# Pedal_Display.net
KiCad netlist of a schematic drawn in Altium Designer
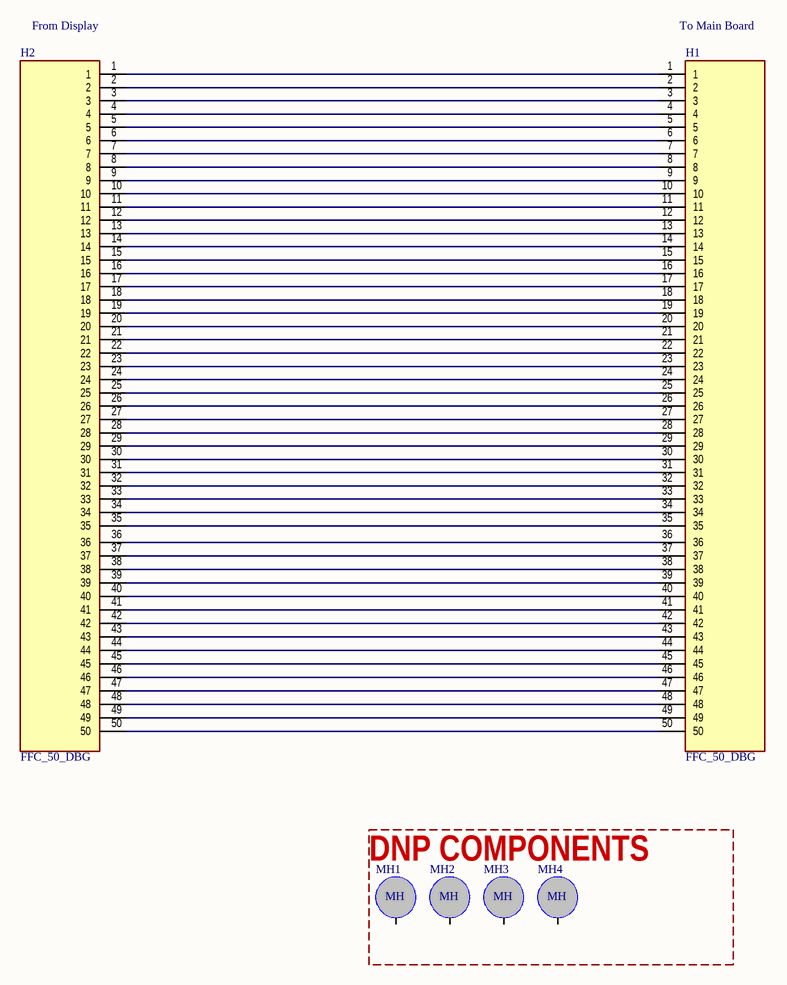
[diagram p0: Pedal_Display.SchDoc]

(export (version "E")
  (design (tool "Eeschema 10.0.6"))
  (components
    (comp (ref "H1")
      (value "FFC_50_DBG")
      (footprint "ProtoStack_H750VBT:FFC_50_DBG")
      (libsource (lib "ProtoStack_H750VBT") (part "FFC_50_DBG"))
    )
    (comp (ref "H2")
      (value "FFC_50_DBG")
      (footprint "ProtoStack_H750VBT:FFC_50_DBG")
      (libsource (lib "") (part "FFC_50_DBG_1"))
    )
    (comp (ref "MH1")
      (value "MountingHole")
      (footprint "ProtoStack_H750VBT:Hole_3mm")
      (libsource (lib "ProtoStack_H750VBT") (part "MountingHole"))
    )
    (comp (ref "MH2")
      (value "MountingHole")
      (footprint "ProtoStack_H750VBT:Hole_3mm")
      (libsource (lib "ProtoStack_H750VBT") (part "MountingHole"))
    )
    (comp (ref "MH3")
      (value "MountingHole")
      (footprint "ProtoStack_H750VBT:Hole_3mm")
      (libsource (lib "ProtoStack_H750VBT") (part "MountingHole"))
    )
    (comp (ref "MH4")
      (value "MountingHole")
      (footprint "ProtoStack_H750VBT:Hole_3mm")
      (libsource (lib "ProtoStack_H750VBT") (part "MountingHole"))
    )
  )
  (nets
    (net (code "1") (name "Net-(H1-Pad1)") (class "Default")
      (node (ref "H1") (pin "1") (pinfunction "1_1") (pintype "passive"))
      (node (ref "H2") (pin "1") (pinfunction "1_1") (pintype "passive"))
    )
    (net (code "2") (name "Net-(H1-Pad2)") (class "Default")
      (node (ref "H1") (pin "2") (pinfunction "2_2") (pintype "passive"))
      (node (ref "H2") (pin "2") (pinfunction "2_2") (pintype "passive"))
    )
    (net (code "3") (name "Net-(H1-Pad3)") (class "Default")
      (node (ref "H1") (pin "3") (pinfunction "3_3") (pintype "passive"))
      (node (ref "H2") (pin "3") (pinfunction "3_3") (pintype "passive"))
    )
    (net (code "4") (name "Net-(H1-Pad4)") (class "Default")
      (node (ref "H1") (pin "4") (pinfunction "4_4") (pintype "passive"))
      (node (ref "H2") (pin "4") (pinfunction "4_4") (pintype "passive"))
    )
    (net (code "5") (name "Net-(H1-Pad5)") (class "Default")
      (node (ref "H1") (pin "5") (pinfunction "5_5") (pintype "passive"))
      (node (ref "H2") (pin "5") (pinfunction "5_5") (pintype "passive"))
    )
    (net (code "6") (name "Net-(H1-Pad6)") (class "Default")
      (node (ref "H1") (pin "6") (pinfunction "6_6") (pintype "passive"))
      (node (ref "H2") (pin "6") (pinfunction "6_6") (pintype "passive"))
    )
    (net (code "7") (name "Net-(H1-Pad7)") (class "Default")
      (node (ref "H1") (pin "7") (pinfunction "7_7") (pintype "passive"))
      (node (ref "H2") (pin "7") (pinfunction "7_7") (pintype "passive"))
    )
    (net (code "8") (name "Net-(H1-Pad8)") (class "Default")
      (node (ref "H1") (pin "8") (pinfunction "8_8") (pintype "passive"))
      (node (ref "H2") (pin "8") (pinfunction "8_8") (pintype "passive"))
    )
    (net (code "9") (name "Net-(H1-Pad9)") (class "Default")
      (node (ref "H1") (pin "9") (pinfunction "9_9") (pintype "passive"))
      (node (ref "H2") (pin "9") (pinfunction "9_9") (pintype "passive"))
    )
    (net (code "10") (name "Net-(H1-Pad10)") (class "Default")
      (node (ref "H1") (pin "10") (pinfunction "10_10") (pintype "passive"))
      (node (ref "H2") (pin "10") (pinfunction "10_10") (pintype "passive"))
    )
    (net (code "11") (name "Net-(H1-Pad11)") (class "Default")
      (node (ref "H1") (pin "11") (pinfunction "11_11") (pintype "passive"))
      (node (ref "H2") (pin "11") (pinfunction "11_11") (pintype "passive"))
    )
    (net (code "12") (name "Net-(H1-Pad12)") (class "Default")
      (node (ref "H1") (pin "12") (pinfunction "12_12") (pintype "passive"))
      (node (ref "H2") (pin "12") (pinfunction "12_12") (pintype "passive"))
    )
    (net (code "13") (name "Net-(H1-Pad13)") (class "Default")
      (node (ref "H1") (pin "13") (pinfunction "13_13") (pintype "passive"))
      (node (ref "H2") (pin "13") (pinfunction "13_13") (pintype "passive"))
    )
    (net (code "14") (name "Net-(H1-Pad14)") (class "Default")
      (node (ref "H1") (pin "14") (pinfunction "14_14") (pintype "passive"))
      (node (ref "H2") (pin "14") (pinfunction "14_14") (pintype "passive"))
    )
    (net (code "15") (name "Net-(H1-Pad15)") (class "Default")
      (node (ref "H1") (pin "15") (pinfunction "15_15") (pintype "passive"))
      (node (ref "H2") (pin "15") (pinfunction "15_15") (pintype "passive"))
    )
    (net (code "16") (name "Net-(H1-Pad16)") (class "Default")
      (node (ref "H1") (pin "16") (pinfunction "16_16") (pintype "passive"))
      (node (ref "H2") (pin "16") (pinfunction "16_16") (pintype "passive"))
    )
    (net (code "17") (name "Net-(H1-Pad17)") (class "Default")
      (node (ref "H1") (pin "17") (pinfunction "17_17") (pintype "passive"))
      (node (ref "H2") (pin "17") (pinfunction "17_17") (pintype "passive"))
    )
    (net (code "18") (name "Net-(H1-Pad18)") (class "Default")
      (node (ref "H1") (pin "18") (pinfunction "18_18") (pintype "passive"))
      (node (ref "H2") (pin "18") (pinfunction "18_18") (pintype "passive"))
    )
    (net (code "19") (name "Net-(H1-Pad19)") (class "Default")
      (node (ref "H1") (pin "19") (pinfunction "19_19") (pintype "passive"))
      (node (ref "H2") (pin "19") (pinfunction "19_19") (pintype "passive"))
    )
    (net (code "20") (name "Net-(H1-Pad20)") (class "Default")
      (node (ref "H1") (pin "20") (pinfunction "20_20") (pintype "passive"))
      (node (ref "H2") (pin "20") (pinfunction "20_20") (pintype "passive"))
    )
    (net (code "21") (name "Net-(H1-Pad21)") (class "Default")
      (node (ref "H1") (pin "21") (pinfunction "21_21") (pintype "passive"))
      (node (ref "H2") (pin "21") (pinfunction "21_21") (pintype "passive"))
    )
    (net (code "22") (name "Net-(H1-Pad22)") (class "Default")
      (node (ref "H1") (pin "22") (pinfunction "22_22") (pintype "passive"))
      (node (ref "H2") (pin "22") (pinfunction "22_22") (pintype "passive"))
    )
    (net (code "23") (name "Net-(H1-Pad23)") (class "Default")
      (node (ref "H1") (pin "23") (pinfunction "23_23") (pintype "passive"))
      (node (ref "H2") (pin "23") (pinfunction "23_23") (pintype "passive"))
    )
    (net (code "24") (name "Net-(H1-Pad24)") (class "Default")
      (node (ref "H1") (pin "24") (pinfunction "24_24") (pintype "passive"))
      (node (ref "H2") (pin "24") (pinfunction "24_24") (pintype "passive"))
    )
    (net (code "25") (name "Net-(H1-Pad25)") (class "Default")
      (node (ref "H1") (pin "25") (pinfunction "25_25") (pintype "passive"))
      (node (ref "H2") (pin "25") (pinfunction "25_25") (pintype "passive"))
    )
    (net (code "26") (name "Net-(H1-Pad26)") (class "Default")
      (node (ref "H1") (pin "26") (pinfunction "26_26") (pintype "passive"))
      (node (ref "H2") (pin "26") (pinfunction "26_26") (pintype "passive"))
    )
    (net (code "27") (name "Net-(H1-Pad27)") (class "Default")
      (node (ref "H1") (pin "27") (pinfunction "27_27") (pintype "passive"))
      (node (ref "H2") (pin "27") (pinfunction "27_27") (pintype "passive"))
    )
    (net (code "28") (name "Net-(H1-Pad28)") (class "Default")
      (node (ref "H1") (pin "28") (pinfunction "28_28") (pintype "passive"))
      (node (ref "H2") (pin "28") (pinfunction "28_28") (pintype "passive"))
    )
    (net (code "29") (name "Net-(H1-Pad29)") (class "Default")
      (node (ref "H1") (pin "29") (pinfunction "29_29") (pintype "passive"))
      (node (ref "H2") (pin "29") (pinfunction "29_29") (pintype "passive"))
    )
    (net (code "30") (name "Net-(H1-Pad30)") (class "Default")
      (node (ref "H1") (pin "30") (pinfunction "30_30") (pintype "passive"))
      (node (ref "H2") (pin "30") (pinfunction "30_30") (pintype "passive"))
    )
    (net (code "31") (name "Net-(H1-Pad31)") (class "Default")
      (node (ref "H1") (pin "31") (pinfunction "31_31") (pintype "passive"))
      (node (ref "H2") (pin "31") (pinfunction "31_31") (pintype "passive"))
    )
    (net (code "32") (name "Net-(H1-Pad32)") (class "Default")
      (node (ref "H1") (pin "32") (pinfunction "32_32") (pintype "passive"))
      (node (ref "H2") (pin "32") (pinfunction "32_32") (pintype "passive"))
    )
    (net (code "33") (name "Net-(H1-Pad33)") (class "Default")
      (node (ref "H1") (pin "33") (pinfunction "33_33") (pintype "passive"))
      (node (ref "H2") (pin "33") (pinfunction "33_33") (pintype "passive"))
    )
    (net (code "34") (name "Net-(H1-Pad34)") (class "Default")
      (node (ref "H1") (pin "34") (pinfunction "34_34") (pintype "passive"))
      (node (ref "H2") (pin "34") (pinfunction "34_34") (pintype "passive"))
    )
    (net (code "35") (name "Net-(H1-Pad35)") (class "Default")
      (node (ref "H1") (pin "35") (pinfunction "35_35") (pintype "passive"))
      (node (ref "H2") (pin "35") (pinfunction "35_35") (pintype "passive"))
    )
    (net (code "36") (name "Net-(H1-Pad36)") (class "Default")
      (node (ref "H1") (pin "36") (pinfunction "36_36") (pintype "passive"))
      (node (ref "H2") (pin "36") (pinfunction "36_36") (pintype "passive"))
    )
    (net (code "37") (name "Net-(H1-Pad37)") (class "Default")
      (node (ref "H1") (pin "37") (pinfunction "37_37") (pintype "passive"))
      (node (ref "H2") (pin "37") (pinfunction "37_37") (pintype "passive"))
    )
    (net (code "38") (name "Net-(H1-Pad38)") (class "Default")
      (node (ref "H1") (pin "38") (pinfunction "38_38") (pintype "passive"))
      (node (ref "H2") (pin "38") (pinfunction "38_38") (pintype "passive"))
    )
    (net (code "39") (name "Net-(H1-Pad39)") (class "Default")
      (node (ref "H1") (pin "39") (pinfunction "39_39") (pintype "passive"))
      (node (ref "H2") (pin "39") (pinfunction "39_39") (pintype "passive"))
    )
    (net (code "40") (name "Net-(H1-Pad40)") (class "Default")
      (node (ref "H1") (pin "40") (pinfunction "40_40") (pintype "passive"))
      (node (ref "H2") (pin "40") (pinfunction "40_40") (pintype "passive"))
    )
    (net (code "41") (name "Net-(H1-Pad41)") (class "Default")
      (node (ref "H1") (pin "41") (pinfunction "41_41") (pintype "passive"))
      (node (ref "H2") (pin "41") (pinfunction "41_41") (pintype "passive"))
    )
    (net (code "42") (name "Net-(H1-Pad42)") (class "Default")
      (node (ref "H1") (pin "42") (pinfunction "42_42") (pintype "passive"))
      (node (ref "H2") (pin "42") (pinfunction "42_42") (pintype "passive"))
    )
    (net (code "43") (name "Net-(H1-Pad43)") (class "Default")
      (node (ref "H1") (pin "43") (pinfunction "43_43") (pintype "passive"))
      (node (ref "H2") (pin "43") (pinfunction "43_43") (pintype "passive"))
    )
    (net (code "44") (name "Net-(H1-Pad44)") (class "Default")
      (node (ref "H1") (pin "44") (pinfunction "44_44") (pintype "passive"))
      (node (ref "H2") (pin "44") (pinfunction "44_44") (pintype "passive"))
    )
    (net (code "45") (name "Net-(H1-Pad45)") (class "Default")
      (node (ref "H1") (pin "45") (pinfunction "45_45") (pintype "passive"))
      (node (ref "H2") (pin "45") (pinfunction "45_45") (pintype "passive"))
    )
    (net (code "46") (name "Net-(H1-Pad46)") (class "Default")
      (node (ref "H1") (pin "46") (pinfunction "46_46") (pintype "passive"))
      (node (ref "H2") (pin "46") (pinfunction "46_46") (pintype "passive"))
    )
    (net (code "47") (name "Net-(H1-Pad47)") (class "Default")
      (node (ref "H1") (pin "47") (pinfunction "47_47") (pintype "passive"))
      (node (ref "H2") (pin "47") (pinfunction "47_47") (pintype "passive"))
    )
    (net (code "48") (name "Net-(H1-Pad48)") (class "Default")
      (node (ref "H1") (pin "48") (pinfunction "48_48") (pintype "passive"))
      (node (ref "H2") (pin "48") (pinfunction "48_48") (pintype "passive"))
    )
    (net (code "49") (name "Net-(H1-Pad49)") (class "Default")
      (node (ref "H1") (pin "49") (pinfunction "49_49") (pintype "passive"))
      (node (ref "H2") (pin "49") (pinfunction "49_49") (pintype "passive"))
    )
    (net (code "50") (name "Net-(H1-Pad50)") (class "Default")
      (node (ref "H1") (pin "50") (pinfunction "50_50") (pintype "passive"))
      (node (ref "H2") (pin "50") (pinfunction "50_50") (pintype "passive"))
    )
    (net (code "51") (name "unconnected-(MH1-Pad0)") (class "Default")
      (node (ref "MH1") (pin "0") (pinfunction "0_0") (pintype "passive"))
    )
    (net (code "52") (name "unconnected-(MH2-Pad0)") (class "Default")
      (node (ref "MH2") (pin "0") (pinfunction "0_0") (pintype "passive"))
    )
    (net (code "53") (name "unconnected-(MH3-Pad0)") (class "Default")
      (node (ref "MH3") (pin "0") (pinfunction "0_0") (pintype "passive"))
    )
    (net (code "54") (name "unconnected-(MH4-Pad0)") (class "Default")
      (node (ref "MH4") (pin "0") (pinfunction "0_0") (pintype "passive"))
    )
  )
)
